# Horn_Board.net
KiCad netlist of a schematic drawn in EAGLE
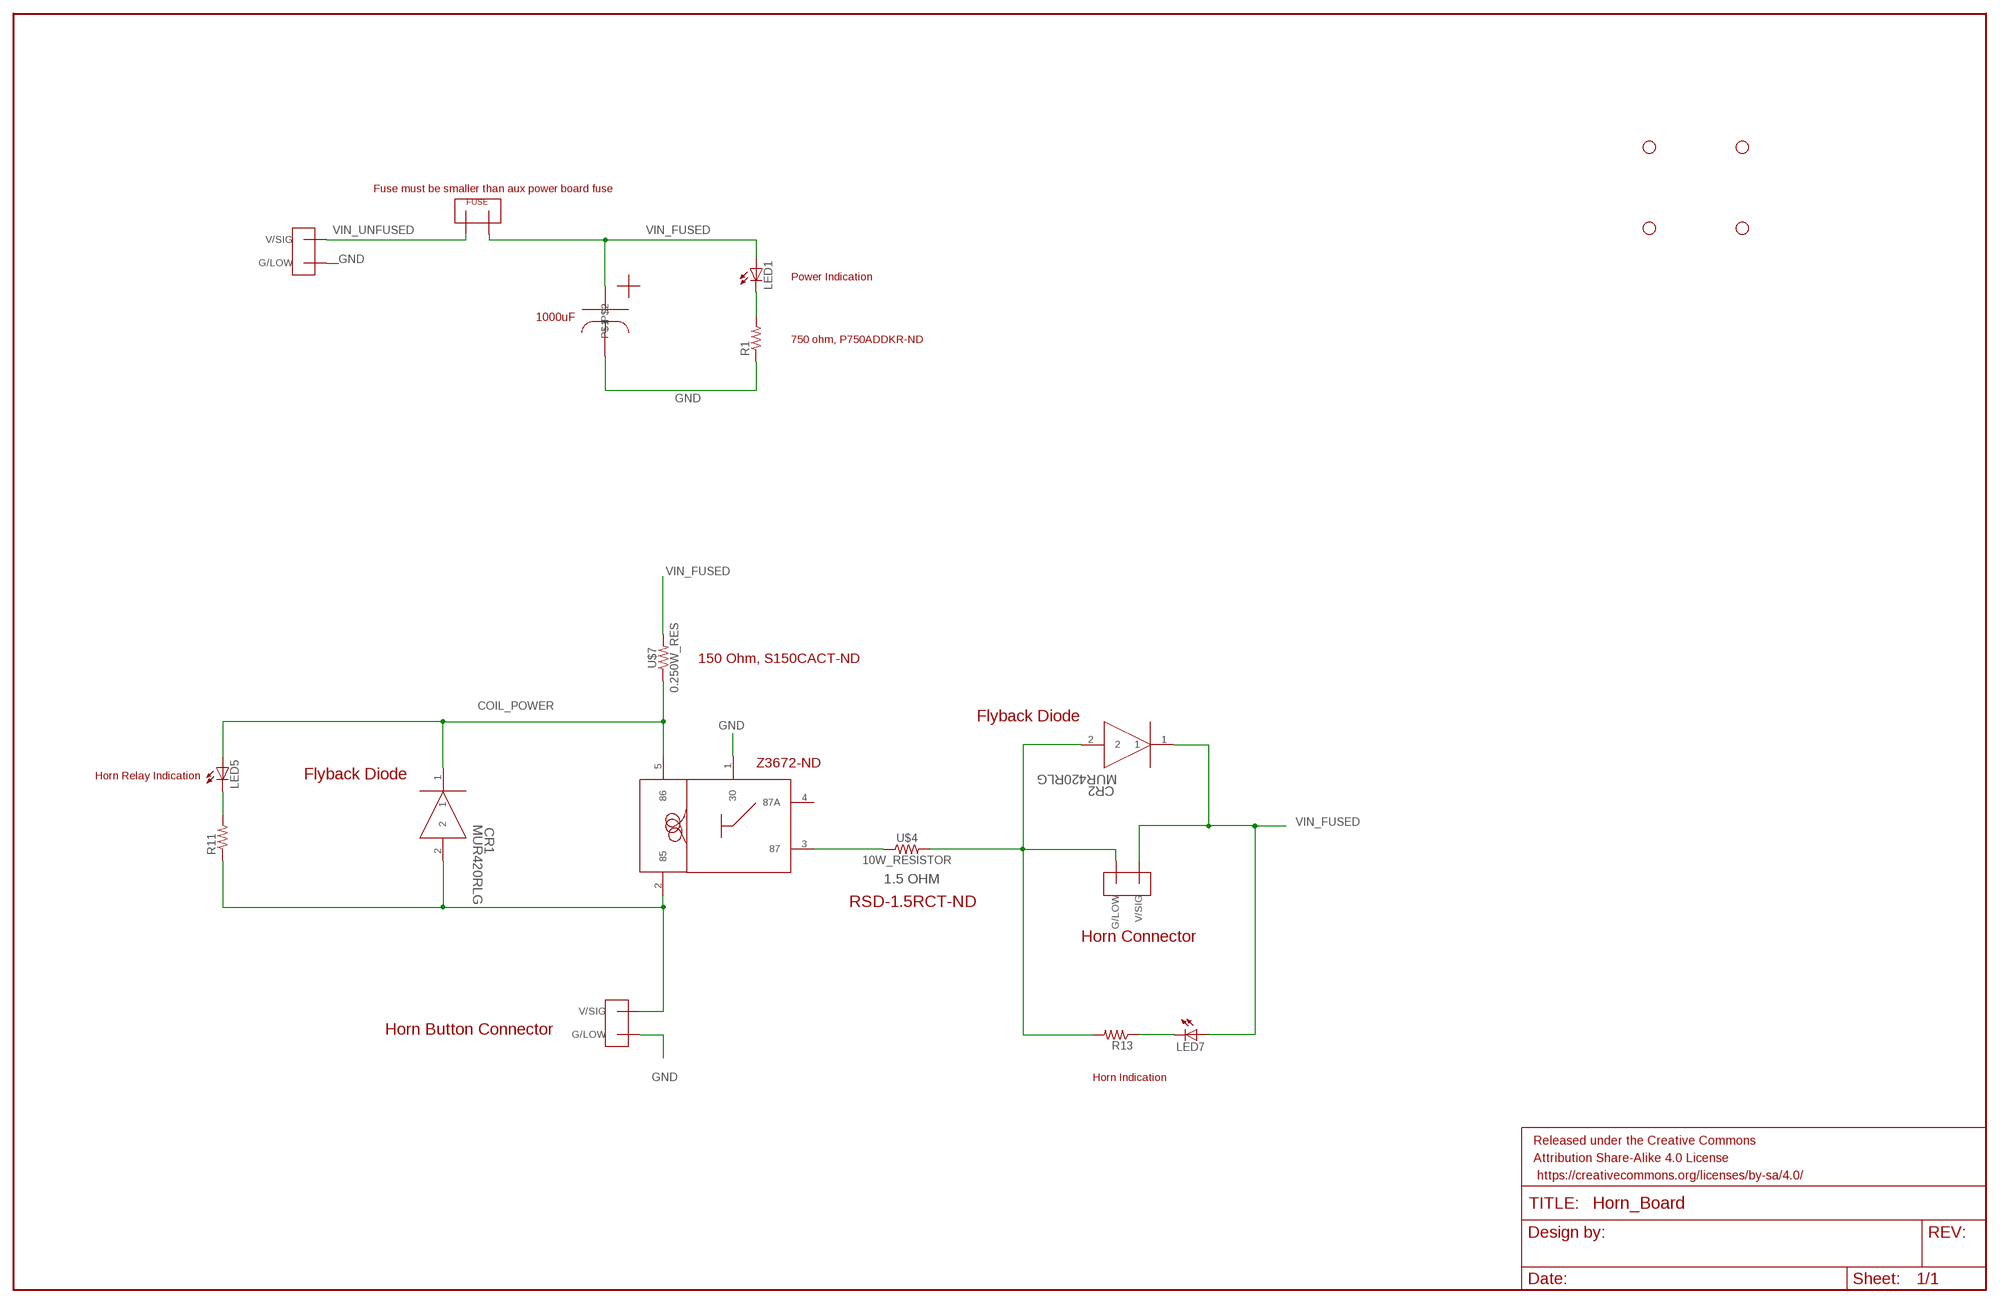
[diagram p0: schematic, sheet 1]

(export (version "E")
  (design (tool "Eeschema 10.0.6"))
  (components
    (comp (ref "CR1")
      (value "MUR420RLG")
      (footprint "eagle-import:DO-201AD")
      (libsource (lib "eagle-import") (part "MUR420RLG"))
    )
    (comp (ref "CR2")
      (value "MUR420RLG")
      (footprint "eagle-import:DO-201AD")
      (libsource (lib "eagle-import") (part "MUR420RLG"))
    )
    (comp (ref "FRAME1")
      (value "FRAME-LEDGER")
      (footprint "eagle-import:CREATIVE_COMMONS")
      (libsource (lib "eagle-import") (part "FRAME-LEDGER"))
    )
    (comp (ref "H1")
      (value "STAND-OFF")
      (footprint "eagle-import:STAND-OFF")
      (libsource (lib "eagle-import") (part "STAND-OFF"))
    )
    (comp (ref "H2")
      (value "STAND-OFF")
      (footprint "eagle-import:STAND-OFF")
      (libsource (lib "eagle-import") (part "STAND-OFF"))
    )
    (comp (ref "H3")
      (value "STAND-OFF")
      (footprint "eagle-import:STAND-OFF")
      (libsource (lib "eagle-import") (part "STAND-OFF"))
    )
    (comp (ref "H4")
      (value "STAND-OFF")
      (footprint "eagle-import:STAND-OFF")
      (libsource (lib "eagle-import") (part "STAND-OFF"))
    )
    (comp (ref "LED1")
      (value "LEDCHIP-LED0805")
      (footprint "eagle-import:CHIP-LED0805")
      (libsource (lib "eagle-import") (part "LEDCHIP-LED0805"))
    )
    (comp (ref "LED5")
      (value "LEDCHIP-LED0805")
      (footprint "eagle-import:CHIP-LED0805")
      (libsource (lib "eagle-import") (part "LEDCHIP-LED0805"))
    )
    (comp (ref "LED7")
      (value "LEDCHIP-LED0805")
      (footprint "eagle-import:CHIP-LED0805")
      (libsource (lib "eagle-import") (part "LEDCHIP-LED0805"))
    )
    (comp (ref "R1")
      (value "R-US_M0805")
      (footprint "eagle-import:M0805")
      (libsource (lib "eagle-import") (part "R-US_M0805"))
    )
    (comp (ref "R11")
      (value "R-US_M0805")
      (footprint "eagle-import:M0805")
      (libsource (lib "eagle-import") (part "R-US_M0805"))
    )
    (comp (ref "R13")
      (value "R-US_M0805")
      (footprint "eagle-import:M0805")
      (libsource (lib "eagle-import") (part "R-US_M0805"))
    )
    (comp (ref "U$1")
      (value "TE770966")
      (footprint "eagle-import:2X1-MATE-N-LOCK")
      (libsource (lib "eagle-import") (part "TE770966"))
    )
    (comp (ref "U$2")
      (value "FUSEMINI-BLADE")
      (footprint "eagle-import:MINI-BLADE-FUSE")
      (libsource (lib "eagle-import") (part "FUSEMINI-BLADE"))
    )
    (comp (ref "U$3")
      (value "OMRON_G5LE-1")
      (footprint "eagle-import:OMRON_G5LE-1")
      (libsource (lib "eagle-import") (part "OMRON_G5LE-1"))
    )
    (comp (ref "U$4")
      (value "10W_RESISTOR")
      (footprint "eagle-import:10W_RESISTOR")
      (libsource (lib "eagle-import") (part "10W_RESISTOR"))
    )
    (comp (ref "U$7")
      (value "0.250W_RES")
      (footprint "eagle-import:AXIAL-0.3")
      (libsource (lib "eagle-import") (part "0.250W_RES"))
    )
    (comp (ref "U$17")
      (value "TE770966")
      (footprint "eagle-import:2X1-MATE-N-LOCK")
      (libsource (lib "eagle-import") (part "TE770966"))
    )
    (comp (ref "U$18")
      (value "TE770966")
      (footprint "eagle-import:2X1-MATE-N-LOCK")
      (libsource (lib "eagle-import") (part "TE770966"))
    )
    (comp (ref "U$22")
      (value "CAPESK108M025AH4EA")
      (footprint "eagle-import:ESK108M025AH4EA")
      (libsource (lib "eagle-import") (part "CAPESK108M025AH4EA"))
    )
  )
  (nets
    (net (code "1") (name "/COIL_POWER") (class "Default")
      (node (ref "CR1") (pin "1") (pinfunction "1_1") (pintype "passive"))
      (node (ref "LED5") (pin "A") (pinfunction "A_A") (pintype "passive"))
      (node (ref "U$3") (pin "5") (pinfunction "86_5") (pintype "bidirectional"))
      (node (ref "U$7") (pin "P$1") (pinfunction "1_P$1") (pintype "passive"))
    )
    (net (code "2") (name "/GND") (class "Default")
      (node (ref "R1") (pin "1") (pinfunction "1_1") (pintype "passive"))
      (node (ref "U$1") (pin "CIRCUIT2") (pinfunction "G/LOW_CIRCUIT2") (pintype "bidirectional"))
      (node (ref "U$17") (pin "CIRCUIT2") (pinfunction "G/LOW_CIRCUIT2") (pintype "bidirectional"))
      (node (ref "U$22") (pin "P$2") (pinfunction "P$2_P$2") (pintype "bidirectional"))
      (node (ref "U$3") (pin "1") (pinfunction "30_1") (pintype "bidirectional"))
    )
    (net (code "3") (name "/VIN_FUSED") (class "Default")
      (node (ref "CR2") (pin "1") (pinfunction "1_1") (pintype "passive"))
      (node (ref "LED1") (pin "A") (pinfunction "A_A") (pintype "passive"))
      (node (ref "LED7") (pin "A") (pinfunction "A_A") (pintype "passive"))
      (node (ref "U$18") (pin "CIRCUIT1") (pinfunction "V/SIG_CIRCUIT1") (pintype "bidirectional"))
      (node (ref "U$2") (pin "OUT") (pinfunction "OUT_OUT") (pintype "bidirectional"))
      (node (ref "U$22") (pin "P$1") (pinfunction "P$1_P$1") (pintype "bidirectional"))
      (node (ref "U$7") (pin "P$2") (pinfunction "2_P$2") (pintype "passive"))
    )
    (net (code "4") (name "/VIN_UNFUSED") (class "Default")
      (node (ref "U$1") (pin "CIRCUIT1") (pinfunction "V/SIG_CIRCUIT1") (pintype "bidirectional"))
      (node (ref "U$2") (pin "IN") (pinfunction "IN_IN") (pintype "bidirectional"))
    )
    (net (code "5") (name "Net-(LED1-PadC)") (class "Default")
      (node (ref "LED1") (pin "C") (pinfunction "C_C") (pintype "passive"))
      (node (ref "R1") (pin "2") (pinfunction "2_2") (pintype "passive"))
    )
    (net (code "6") (name "Net-(LED5-PadC)") (class "Default")
      (node (ref "LED5") (pin "C") (pinfunction "C_C") (pintype "passive"))
      (node (ref "R11") (pin "2") (pinfunction "2_2") (pintype "passive"))
    )
    (net (code "7") (name "Net-(LED7-PadC)") (class "Default")
      (node (ref "LED7") (pin "C") (pinfunction "C_C") (pintype "passive"))
      (node (ref "R13") (pin "1") (pinfunction "1_1") (pintype "passive"))
    )
    (net (code "8") (name "Net-(U$3-87)") (class "Default")
      (node (ref "U$3") (pin "3") (pinfunction "87_3") (pintype "bidirectional"))
      (node (ref "U$4") (pin "P$1") (pinfunction "1_P$1") (pintype "passive"))
    )
    (net (code "9") (name "Net-(U$17-V{slash}SIG)") (class "Default")
      (node (ref "CR1") (pin "2") (pinfunction "2_2") (pintype "passive"))
      (node (ref "R11") (pin "1") (pinfunction "1_1") (pintype "passive"))
      (node (ref "U$17") (pin "CIRCUIT1") (pinfunction "V/SIG_CIRCUIT1") (pintype "bidirectional"))
      (node (ref "U$3") (pin "2") (pinfunction "85_2") (pintype "bidirectional"))
    )
    (net (code "10") (name "Net-(U$18-G{slash}LOW)") (class "Default")
      (node (ref "CR2") (pin "2") (pinfunction "2_2") (pintype "passive"))
      (node (ref "R13") (pin "2") (pinfunction "2_2") (pintype "passive"))
      (node (ref "U$18") (pin "CIRCUIT2") (pinfunction "G/LOW_CIRCUIT2") (pintype "bidirectional"))
      (node (ref "U$4") (pin "P$2") (pinfunction "2_P$2") (pintype "passive"))
    )
    (net (code "11") (name "unconnected-(U$3-87A-Pad4)") (class "Default")
      (node (ref "U$3") (pin "4") (pinfunction "87A_4") (pintype "bidirectional"))
    )
  )
)
